# Headphone.net
KiCad netlist of a schematic drawn in Altium Designer
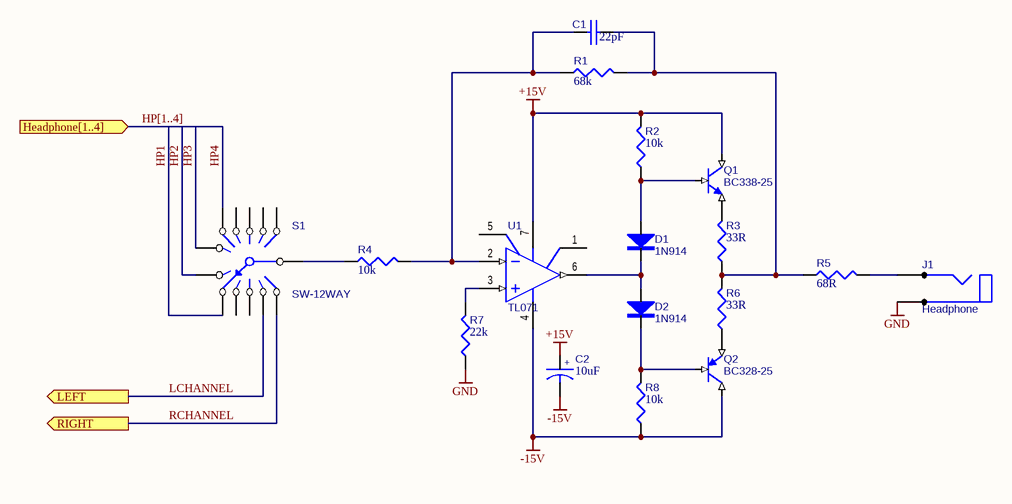
[diagram p0:  Headphone.SchDoc]

(export (version "E")
  (design (tool "Eeschema 10.0.6"))
  (components
    (comp (ref "C1")
      (value "22pF")
      (footprint "RAD0.2")
      (description "Capacitor")
      (libsource (lib "*") (part "CAP"))
    )
    (comp (ref "C2")
      (value "10uF")
      (footprint "RB.2/.4")
      (description "Bi-Polar Capacitor")
      (libsource (lib "*") (part "CAPACITOR POL"))
    )
    (comp (ref "D1")
      (value "1N914")
      (footprint "DIODE0.4")
      (description "Diode")
      (libsource (lib "*") (part "1N914"))
    )
    (comp (ref "D2")
      (value "1N914")
      (footprint "DIODE0.4")
      (description "Diode")
      (libsource (lib "*") (part "1N914"))
    )
    (comp (ref "J1")
      (value "Headphone")
      (footprint "JACK-6.25MM")
      (libsource (lib "*") (part "PHONEJACK MONO"))
    )
    (comp (ref "Q1")
      (value "BC338-25")
      (footprint "TO-92A")
      (description "NPN BJT")
      (libsource (lib "*") (part "BC338-25"))
    )
    (comp (ref "Q2")
      (value "BC328-25")
      (footprint "TO-92A")
      (description "PNP BJT")
      (libsource (lib "*") (part "BC328-25"))
    )
    (comp (ref "R1")
      (value "68k")
      (footprint "AXIAL0.4")
      (description "Resistor")
      (libsource (lib "") (part "RES1_1"))
    )
    (comp (ref "R2")
      (value "10k")
      (footprint "AXIAL0.4")
      (description "Resistor")
      (libsource (lib "*") (part "RES1"))
    )
    (comp (ref "R3")
      (value "33R")
      (footprint "AXIAL0.4")
      (description "Resistor")
      (libsource (lib "*") (part "RES1"))
    )
    (comp (ref "R4")
      (value "10k")
      (footprint "AXIAL0.4")
      (description "Resistor")
      (libsource (lib "") (part "RES1_1"))
    )
    (comp (ref "R5")
      (value "68R")
      (footprint "AXIAL0.4")
      (description "Resistor")
      (libsource (lib "") (part "RES1_1"))
    )
    (comp (ref "R6")
      (value "33R")
      (footprint "AXIAL0.4")
      (description "Resistor")
      (libsource (lib "*") (part "RES1"))
    )
    (comp (ref "R7")
      (value "22k")
      (footprint "AXIAL0.4")
      (description "Resistor")
      (libsource (lib "*") (part "RES1"))
    )
    (comp (ref "R8")
      (value "10k")
      (footprint "AXIAL0.4")
      (description "Resistor")
      (libsource (lib "*") (part "RES1"))
    )
    (comp (ref "S1") (value "SW-12WAY") (footprint "SW-12WAY") (libsource (lib "*") (part "SW-12WAY")))
    (comp (ref "U1")
      (value "TL071")
      (footprint "DIP8")
      (description "Low-Noise  JFET-Input Operational Amplifiers")
      (libsource (lib "*") (part "TL071"))
    )
  )
  (nets
    (net (code "1") (name "+15V") (class "Default")
      (node (ref "C2") (pin "1") (pinfunction "1_1") (pintype "passive"))
      (node (ref "Q1") (pin "1") (pinfunction "C_1") (pintype "input"))
      (node (ref "R2") (pin "2") (pinfunction "2_2") (pintype "passive"))
      (node (ref "U1") (pin "7") (pinfunction "VCC+_7") (pintype "power_in"))
    )
    (net (code "2") (name "-15V") (class "Default")
      (node (ref "C2") (pin "2") (pinfunction "2_2") (pintype "passive"))
      (node (ref "Q2") (pin "1") (pinfunction "C_1") (pintype "input"))
      (node (ref "R8") (pin "1") (pinfunction "1_1") (pintype "passive"))
      (node (ref "U1") (pin "4") (pinfunction "VCC-_4") (pintype "power_in"))
    )
    (net (code "3") (name "/HP1") (class "Default")
      (node (ref "S1") (pin "8") (pinfunction "8_8") (pintype "passive"))
    )
    (net (code "4") (name "/HP2") (class "Default")
      (node (ref "S1") (pin "7") (pinfunction "7_7") (pintype "passive"))
    )
    (net (code "5") (name "/HP3") (class "Default")
      (node (ref "S1") (pin "6") (pinfunction "6_6") (pintype "passive"))
    )
    (net (code "6") (name "/HP4") (class "Default")
      (node (ref "S1") (pin "5") (pinfunction "5_5") (pintype "passive"))
    )
    (net (code "8") (name "/LCHANNEL") (class "Default")
      (node (ref "S1") (pin "11") (pinfunction "11_11") (pintype "passive"))
    )
    (net (code "9") (name "/RCHANNEL") (class "Default")
      (node (ref "S1") (pin "12") (pinfunction "12_12") (pintype "passive"))
    )
    (net (code "10") (name "GND") (class "Default")
      (node (ref "J1") (pin "3") (pinfunction "C_3") (pintype "passive"))
      (node (ref "R7") (pin "1") (pinfunction "1_1") (pintype "passive"))
    )
    (net (code "11") (name "Net-(C1-Pad2)") (class "Default")
      (node (ref "C1") (pin "2") (pinfunction "2_2") (pintype "passive"))
      (node (ref "R1") (pin "2") (pinfunction "2_2") (pintype "passive"))
      (node (ref "R3") (pin "1") (pinfunction "1_1") (pintype "passive"))
      (node (ref "R5") (pin "1") (pinfunction "1_1") (pintype "passive"))
      (node (ref "R6") (pin "2") (pinfunction "2_2") (pintype "passive"))
    )
    (net (code "12") (name "Net-(D1-A)") (class "Default")
      (node (ref "D1") (pin "1") (pinfunction "A_1") (pintype "passive"))
      (node (ref "Q1") (pin "2") (pinfunction "B_2") (pintype "input"))
      (node (ref "R2") (pin "1") (pinfunction "1_1") (pintype "passive"))
    )
    (net (code "13") (name "Net-(D1-K)") (class "Default")
      (node (ref "D1") (pin "2") (pinfunction "K_2") (pintype "passive"))
      (node (ref "D2") (pin "1") (pinfunction "A_1") (pintype "passive"))
      (node (ref "U1") (pin "6") (pinfunction "OUT_6") (pintype "output"))
    )
    (net (code "14") (name "Net-(D2-K)") (class "Default")
      (node (ref "D2") (pin "2") (pinfunction "K_2") (pintype "passive"))
      (node (ref "Q2") (pin "2") (pinfunction "B_2") (pintype "input"))
      (node (ref "R8") (pin "2") (pinfunction "2_2") (pintype "passive"))
    )
    (net (code "15") (name "Net-(J1-A)") (class "Default")
      (node (ref "J1") (pin "1") (pinfunction "A_1") (pintype "passive"))
      (node (ref "R5") (pin "2") (pinfunction "2_2") (pintype "passive"))
    )
    (net (code "16") (name "Net-(Q1-E)") (class "Default")
      (node (ref "Q1") (pin "3") (pinfunction "E_3") (pintype "input"))
      (node (ref "R3") (pin "2") (pinfunction "2_2") (pintype "passive"))
    )
    (net (code "17") (name "Net-(Q2-E)") (class "Default")
      (node (ref "Q2") (pin "3") (pinfunction "E_3") (pintype "input"))
      (node (ref "R6") (pin "1") (pinfunction "1_1") (pintype "passive"))
    )
    (net (code "18") (name "Net-(R4-Pad1)") (class "Default")
      (node (ref "R4") (pin "1") (pinfunction "1_1") (pintype "passive"))
      (node (ref "S1") (pin "13") (pinfunction "13_13") (pintype "passive"))
    )
    (net (code "19") (name "Net-(U1-IN+)") (class "Default")
      (node (ref "R7") (pin "2") (pinfunction "2_2") (pintype "passive"))
      (node (ref "U1") (pin "3") (pinfunction "IN+_3") (pintype "input"))
    )
    (net (code "20") (name "Net-(U1-IN-)") (class "Default")
      (node (ref "C1") (pin "1") (pinfunction "1_1") (pintype "passive"))
      (node (ref "R1") (pin "1") (pinfunction "1_1") (pintype "passive"))
      (node (ref "R4") (pin "2") (pinfunction "2_2") (pintype "passive"))
      (node (ref "U1") (pin "2") (pinfunction "IN-_2") (pintype "input"))
    )
    (net (code "21") (name "unconnected-(S1-Pad1)") (class "Default")
      (node (ref "S1") (pin "1") (pinfunction "1_1") (pintype "passive"))
    )
    (net (code "22") (name "unconnected-(S1-Pad2)") (class "Default")
      (node (ref "S1") (pin "2") (pinfunction "2_2") (pintype "passive"))
    )
    (net (code "23") (name "unconnected-(S1-Pad3)") (class "Default")
      (node (ref "S1") (pin "3") (pinfunction "3_3") (pintype "passive"))
    )
    (net (code "24") (name "unconnected-(S1-Pad4)") (class "Default")
      (node (ref "S1") (pin "4") (pinfunction "4_4") (pintype "passive"))
    )
    (net (code "25") (name "unconnected-(S1-Pad9)") (class "Default")
      (node (ref "S1") (pin "9") (pinfunction "9_9") (pintype "passive"))
    )
    (net (code "26") (name "unconnected-(S1-Pad10)") (class "Default")
      (node (ref "S1") (pin "10") (pinfunction "10_10") (pintype "passive"))
    )
    (net (code "27") (name "unconnected-(U1-N1{slash}O.S.-Pad1)") (class "Default")
      (node (ref "U1") (pin "1") (pinfunction "N1/O.S._1") (pintype "passive"))
    )
    (net (code "28") (name "unconnected-(U1-O.S._N2-Pad5)") (class "Default")
      (node (ref "U1") (pin "5") (pinfunction "O.S._N2_5") (pintype "passive"))
    )
  )
)
